# S2_Mini_Benchtop_Test_Board.net
KiCad netlist of a schematic drawn in EAGLE
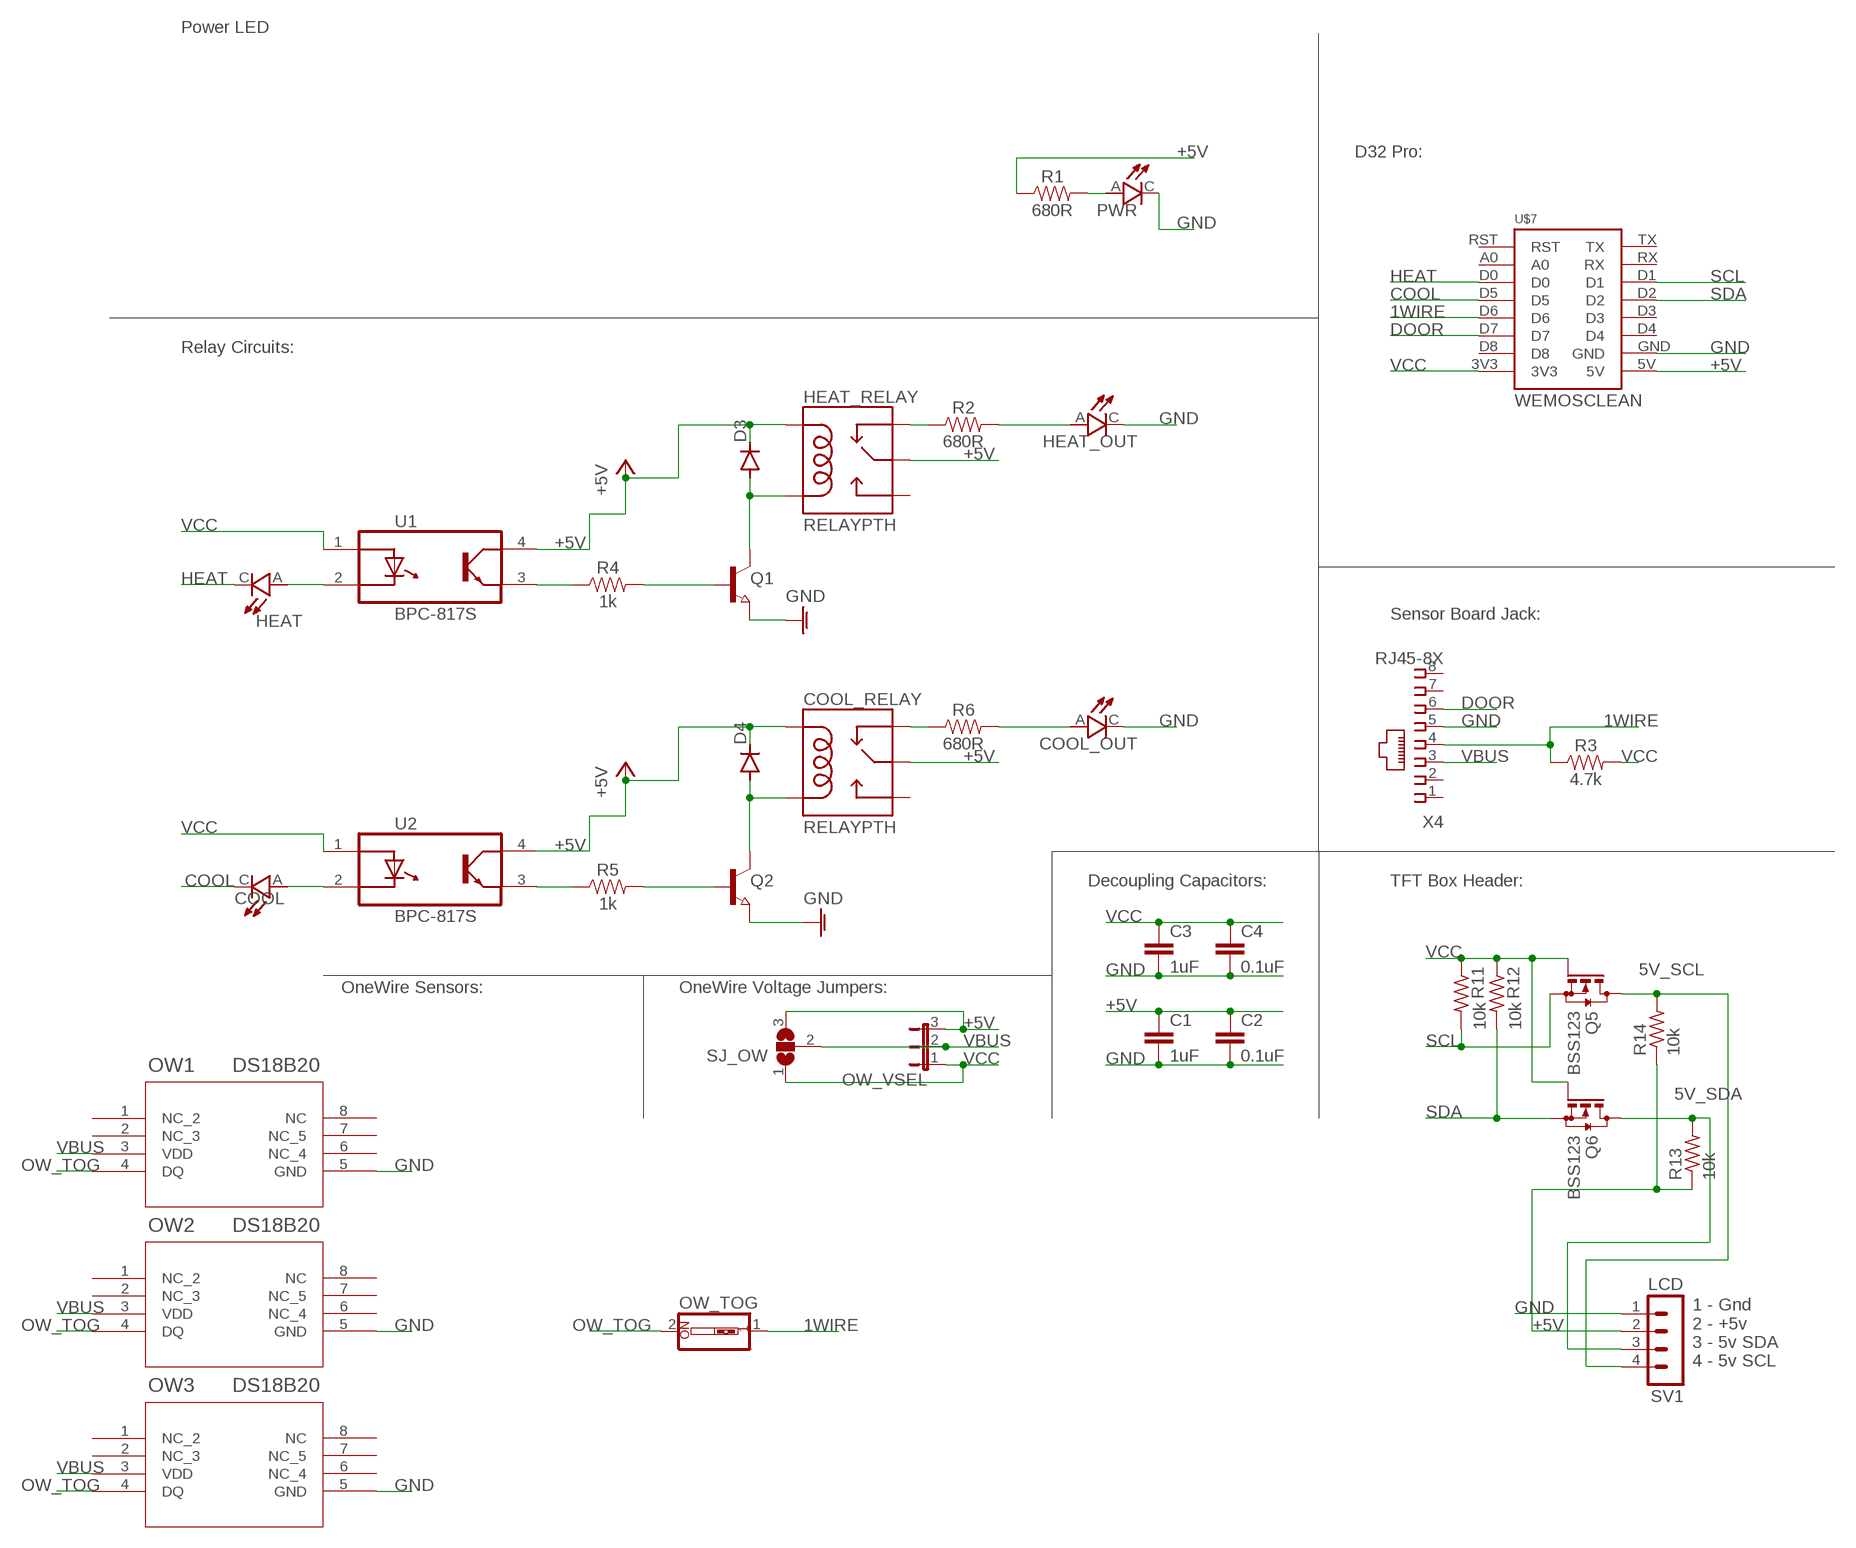
[diagram p0: schematic, sheet 1]

(export (version "E")
  (design (tool "Eeschema 10.0.6"))
  (components
    (comp (ref "C1")
      (value "1uF")
      (footprint "eagle-import:SMD-0805")
      (fields (field (name "LCSC_PART") "C28323"))
      (libsource (lib "eagle-import") (part "CAP_SMD0805"))
    )
    (comp (ref "C2")
      (value "0.1uF")
      (footprint "eagle-import:SMD-0805")
      (fields (field (name "LCSC_PART") "C49678"))
      (libsource (lib "eagle-import") (part "CAP_SMD0805"))
    )
    (comp (ref "C3")
      (value "1uF")
      (footprint "eagle-import:SMD-0805")
      (fields (field (name "LCSC_PART") "C28323"))
      (libsource (lib "eagle-import") (part "CAP_SMD0805"))
    )
    (comp (ref "C4")
      (value "0.1uF")
      (footprint "eagle-import:SMD-0805")
      (fields (field (name "LCSC_PART") "C49678"))
      (libsource (lib "eagle-import") (part "CAP_SMD0805"))
    )
    (comp (ref "COOL")
      (value "LED_0603LED_SMD_0603")
      (footprint "eagle-import:LED_SMD_0603")
      (fields (field (name "LCSC_PART") "C2286") (field (name "LCSC_PART_1") "C2286"))
      (libsource (lib "eagle-import") (part "LED_0603LED_SMD_0603"))
    )
    (comp (ref "COOL_OUT")
      (value "LED_0603LED_SMD_0603")
      (footprint "eagle-import:LED_SMD_0603")
      (fields (field (name "LCSC_PART") "C2286"))
      (libsource (lib "eagle-import") (part "LED_0603LED_SMD_0603"))
    )
    (comp (ref "COOL_RELAY")
      (value "RELAYPTH")
      (footprint "eagle-import:SRD-05VDC-SL-C")
      (fields (field (name "LCSC_PART") "C35449"))
      (libsource (lib "eagle-import") (part "RELAYPTH"))
    )
    (comp (ref "D3")
      (value "DIODE-DO214AC")
      (footprint "eagle-import:DO214AC")
      (fields (field (name "LCSC_PART") "C95872"))
      (libsource (lib "eagle-import") (part "DIODE-DO214AC"))
    )
    (comp (ref "D4")
      (value "DIODE-DO214AC")
      (footprint "eagle-import:DO214AC")
      (fields (field (name "LCSC_PART") "C95872"))
      (libsource (lib "eagle-import") (part "DIODE-DO214AC"))
    )
    (comp (ref "HEAT")
      (value "LED_0603LED_SMD_0603")
      (footprint "eagle-import:LED_SMD_0603")
      (fields (field (name "LCSC_PART") "C2286") (field (name "LCSC_PART_1") "C2286"))
      (libsource (lib "eagle-import") (part "LED_0603LED_SMD_0603"))
    )
    (comp (ref "HEAT_OUT")
      (value "LED_0603LED_SMD_0603")
      (footprint "eagle-import:LED_SMD_0603")
      (fields (field (name "LCSC_PART") "C2286"))
      (libsource (lib "eagle-import") (part "LED_0603LED_SMD_0603"))
    )
    (comp (ref "HEAT_RELAY")
      (value "RELAYPTH")
      (footprint "eagle-import:SRD-05VDC-SL-C")
      (fields (field (name "LCSC_PART") "C35449"))
      (libsource (lib "eagle-import") (part "RELAYPTH"))
    )
    (comp (ref "OW1")
      (value "DS18B20")
      (footprint "eagle-import:21-0041B_8_MXM")
      (fields
        (field (name "LCSC_PART") "C695837")
        (field (name "MANUFACTURER_PART_NUMBER") "DS18B20Z+T&R")
        (field (name "COPYRIGHT") "Copyright (C) 2024 Ultra Librarian. All rights reserved.")
      )
      (libsource (lib "eagle-import") (part "DS18B20Z+T&R"))
    )
    (comp (ref "OW2")
      (value "DS18B20")
      (footprint "eagle-import:21-0041B_8_MXM")
      (fields
        (field (name "LCSC_PART") "C695837")
        (field (name "MANUFACTURER_PART_NUMBER") "DS18B20Z+T&R")
        (field (name "COPYRIGHT") "Copyright (C) 2024 Ultra Librarian. All rights reserved.")
      )
      (libsource (lib "eagle-import") (part "DS18B20Z+T&R"))
    )
    (comp (ref "OW3")
      (value "DS18B20")
      (footprint "eagle-import:21-0041B_8_MXM")
      (fields
        (field (name "LCSC_PART") "C695837")
        (field (name "MANUFACTURER_PART_NUMBER") "DS18B20Z+T&R")
        (field (name "COPYRIGHT") "Copyright (C) 2024 Ultra Librarian. All rights reserved.")
      )
      (libsource (lib "eagle-import") (part "DS18B20Z+T&R"))
    )
    (comp (ref "OW_TOG")
      (value "SW_DIP-1")
      (footprint "eagle-import:EDG-01")
      (fields (field (name "LCSC_PART") "C126888"))
      (libsource (lib "eagle-import") (part "SW_DIP-1"))
    )
    (comp (ref "OW_VSEL")
      (value "JP2ENOLABEL")
      (footprint "eagle-import:JP2-NOLABEL")
      (fields (field (name "LCSC_PART") "C2937625"))
      (libsource (lib "eagle-import") (part "JP2ENOLABEL"))
    )
    (comp (ref "PWR")
      (value "LED_0603LED_SMD_0603")
      (footprint "eagle-import:LED_SMD_0603")
      (fields (field (name "LCSC_PART") "C2286") (field (name "LCSC_PART_1") "C2286"))
      (libsource (lib "eagle-import") (part "LED_0603LED_SMD_0603"))
    )
    (comp (ref "Q1")
      (value "NPN-TRANSISTOR_SOT23")
      (footprint "eagle-import:SOT23")
      (fields (field (name "LCSC_PART") "C20526"))
      (libsource (lib "eagle-import") (part "NPN-TRANSISTOR_SOT23"))
    )
    (comp (ref "Q2")
      (value "NPN-TRANSISTOR_SOT23")
      (footprint "eagle-import:SOT23")
      (fields (field (name "LCSC_PART") "C20526"))
      (libsource (lib "eagle-import") (part "NPN-TRANSISTOR_SOT23"))
    )
    (comp (ref "Q5")
      (value "BSS123")
      (footprint "eagle-import:SOT23")
      (fields (field (name "LCSC_PART") "C79015"))
      (libsource (lib "eagle-import") (part "BSS123"))
    )
    (comp (ref "Q6")
      (value "BSS123")
      (footprint "eagle-import:SOT23")
      (fields (field (name "LCSC_PART") "C79015"))
      (libsource (lib "eagle-import") (part "BSS123"))
    )
    (comp (ref "R1")
      (value "680R")
      (footprint "eagle-import:SMD-0805")
      (fields (field (name "LCSC_PART") "C17798"))
      (libsource (lib "eagle-import") (part "RES_SMD0805"))
    )
    (comp (ref "R2")
      (value "680R")
      (footprint "eagle-import:SMD-0805")
      (fields (field (name "LCSC_PART") "C17798"))
      (libsource (lib "eagle-import") (part "RES_SMD0805"))
    )
    (comp (ref "R3")
      (value "4.7k")
      (footprint "eagle-import:SMD-0805")
      (fields (field (name "LCSC_PART") "C17673"))
      (libsource (lib "eagle-import") (part "RES_SMD0805"))
    )
    (comp (ref "R4")
      (value "1k")
      (footprint "eagle-import:SMD-0805")
      (fields (field (name "LCSC_PART") "C17513"))
      (libsource (lib "eagle-import") (part "RES_SMD0805"))
    )
    (comp (ref "R5")
      (value "1k")
      (footprint "eagle-import:SMD-0805")
      (fields (field (name "LCSC_PART") "C17513"))
      (libsource (lib "eagle-import") (part "RES_SMD0805"))
    )
    (comp (ref "R6")
      (value "680R")
      (footprint "eagle-import:SMD-0805")
      (fields (field (name "LCSC_PART") "C17798"))
      (libsource (lib "eagle-import") (part "RES_SMD0805"))
    )
    (comp (ref "R11")
      (value "10k")
      (footprint "eagle-import:R0805")
      (fields (field (name "LCSC_PART") "C17902"))
      (libsource (lib "eagle-import") (part "R-US_R0805"))
    )
    (comp (ref "R12")
      (value "10k")
      (footprint "eagle-import:R0805")
      (fields (field (name "LCSC_PART") "C17902"))
      (libsource (lib "eagle-import") (part "R-US_R0805"))
    )
    (comp (ref "R13")
      (value "10k")
      (footprint "eagle-import:R0805")
      (fields (field (name "LCSC_PART") "C17902"))
      (libsource (lib "eagle-import") (part "R-US_R0805"))
    )
    (comp (ref "R14")
      (value "10k")
      (footprint "eagle-import:R0805")
      (fields (field (name "LCSC_PART") "C17902"))
      (libsource (lib "eagle-import") (part "R-US_R0805"))
    )
    (comp (ref "SJ_OW")
      (value "SJ2W")
      (footprint "eagle-import:SJ_2")
      (libsource (lib "eagle-import") (part "SJ2W"))
    )
    (comp (ref "SV1")
      (value "LCD")
      (footprint "eagle-import:HDR-4_VERT")
      (fields (field (name "LCSC_PART") "C2691448"))
      (libsource (lib "eagle-import") (part "HDR-4"))
    )
    (comp (ref "U$7")
      (value "WEMOSCLEAN")
      (footprint "eagle-import:WEMOS-CLEAN")
      (libsource (lib "eagle-import") (part "WEMOSCLEAN"))
    )
    (comp (ref "U1")
      (value "BPC-817S")
      (footprint "eagle-import:SOIC127P700X210-4N")
      (fields (field (name "LCSC_PART") "C106900"))
      (libsource (lib "eagle-import") (part "BPC-817S"))
    )
    (comp (ref "U2")
      (value "BPC-817S")
      (footprint "eagle-import:SOIC127P700X210-4N")
      (fields (field (name "LCSC_PART") "C106900"))
      (libsource (lib "eagle-import") (part "BPC-817S"))
    )
    (comp (ref "X4")
      (value "RJ45-8X")
      (footprint "eagle-import:RJ45-NO-SHIELD")
      (fields
        (field (name "LCSC_PART") "C3000197")
        (field (name "JLC_Y") "7.55")
        (field (name "LCSC_PART_1") "C3000197")
      )
      (libsource (lib "eagle-import") (part "RJ45-8X"))
    )
  )
  (nets
    (net (code "1") (name "+5V") (class "Default")
      (node (ref "C1") (pin "1") (pinfunction "1_1") (pintype "passive"))
      (node (ref "C2") (pin "1") (pinfunction "1_1") (pintype "passive"))
      (node (ref "COOL_RELAY") (pin "COIL1") (pinfunction "COIL1_COIL1") (pintype "bidirectional"))
      (node (ref "COOL_RELAY") (pin "SWCOMMON") (pinfunction "SWCOMMON_SWCOMMON") (pintype "bidirectional"))
      (node (ref "D3") (pin "C") (pinfunction "C_C") (pintype "passive"))
      (node (ref "D4") (pin "C") (pinfunction "C_C") (pintype "passive"))
      (node (ref "HEAT_RELAY") (pin "COIL1") (pinfunction "COIL1_COIL1") (pintype "bidirectional"))
      (node (ref "HEAT_RELAY") (pin "SWCOMMON") (pinfunction "SWCOMMON_SWCOMMON") (pintype "bidirectional"))
      (node (ref "OW_VSEL") (pin "3") (pinfunction "3_3") (pintype "passive"))
      (node (ref "R1") (pin "1") (pinfunction "1_1") (pintype "passive"))
      (node (ref "R13") (pin "1") (pinfunction "1_1") (pintype "passive"))
      (node (ref "R14") (pin "1") (pinfunction "1_1") (pintype "passive"))
      (node (ref "SJ_OW") (pin "3") (pinfunction "3_3") (pintype "passive"))
      (node (ref "SV1") (pin "2") (pinfunction "2_2") (pintype "passive"))
      (node (ref "U$7") (pin "5V") (pinfunction "5V_5V") (pintype "bidirectional"))
      (node (ref "U1") (pin "4") (pinfunction "CO_4") (pintype "passive"))
      (node (ref "U2") (pin "4") (pinfunction "CO_4") (pintype "passive"))
    )
    (net (code "2") (name "/1WIRE") (class "Default")
      (node (ref "OW_TOG") (pin "1") (pinfunction "1_1") (pintype "passive"))
      (node (ref "R3") (pin "1") (pinfunction "1_1") (pintype "passive"))
      (node (ref "U$7") (pin "D6") (pinfunction "D6_D6") (pintype "bidirectional"))
      (node (ref "X4") (pin "4") (pinfunction "4_4") (pintype "passive"))
    )
    (net (code "3") (name "/5V_SCL") (class "Default")
      (node (ref "Q5") (pin "3") (pinfunction "D_3") (pintype "passive"))
      (node (ref "R14") (pin "2") (pinfunction "2_2") (pintype "passive"))
      (node (ref "SV1") (pin "4") (pinfunction "4_4") (pintype "passive"))
    )
    (net (code "4") (name "/5V_SDA") (class "Default")
      (node (ref "Q6") (pin "3") (pinfunction "D_3") (pintype "passive"))
      (node (ref "R13") (pin "2") (pinfunction "2_2") (pintype "passive"))
      (node (ref "SV1") (pin "3") (pinfunction "3_3") (pintype "passive"))
    )
    (net (code "5") (name "/COOL") (class "Default")
      (node (ref "COOL") (pin "C") (pinfunction "C_C") (pintype "passive"))
      (node (ref "U$7") (pin "D5") (pinfunction "D5_D5") (pintype "bidirectional"))
    )
    (net (code "6") (name "/DOOR") (class "Default")
      (node (ref "U$7") (pin "D7") (pinfunction "D7_D7") (pintype "bidirectional"))
      (node (ref "X4") (pin "6") (pinfunction "6_6") (pintype "passive"))
    )
    (net (code "7") (name "/HEAT") (class "Default")
      (node (ref "HEAT") (pin "C") (pinfunction "C_C") (pintype "passive"))
      (node (ref "U$7") (pin "D0") (pinfunction "D0_D0") (pintype "bidirectional"))
    )
    (net (code "8") (name "/OW_TOG") (class "Default")
      (node (ref "OW1") (pin "4") (pinfunction "DQ_4") (pintype "bidirectional"))
      (node (ref "OW2") (pin "4") (pinfunction "DQ_4") (pintype "bidirectional"))
      (node (ref "OW3") (pin "4") (pinfunction "DQ_4") (pintype "bidirectional"))
      (node (ref "OW_TOG") (pin "2") (pinfunction "2_2") (pintype "passive"))
    )
    (net (code "9") (name "/SCL") (class "Default")
      (node (ref "Q5") (pin "2") (pinfunction "S_2") (pintype "passive"))
      (node (ref "R11") (pin "2") (pinfunction "2_2") (pintype "passive"))
      (node (ref "U$7") (pin "D1") (pinfunction "D1_D1") (pintype "bidirectional"))
    )
    (net (code "10") (name "/SDA") (class "Default")
      (node (ref "Q6") (pin "2") (pinfunction "S_2") (pintype "passive"))
      (node (ref "R12") (pin "2") (pinfunction "2_2") (pintype "passive"))
      (node (ref "U$7") (pin "D2") (pinfunction "D2_D2") (pintype "bidirectional"))
    )
    (net (code "11") (name "/VBUS") (class "Default")
      (node (ref "OW1") (pin "3") (pinfunction "VDD_3") (pintype "power_in"))
      (node (ref "OW2") (pin "3") (pinfunction "VDD_3") (pintype "power_in"))
      (node (ref "OW3") (pin "3") (pinfunction "VDD_3") (pintype "power_in"))
      (node (ref "OW_VSEL") (pin "2") (pinfunction "2_2") (pintype "passive"))
      (node (ref "SJ_OW") (pin "2") (pinfunction "2_2") (pintype "passive"))
      (node (ref "X4") (pin "3") (pinfunction "3_3") (pintype "passive"))
    )
    (net (code "12") (name "/VCC") (class "Default")
      (node (ref "C3") (pin "1") (pinfunction "1_1") (pintype "passive"))
      (node (ref "C4") (pin "1") (pinfunction "1_1") (pintype "passive"))
      (node (ref "OW_VSEL") (pin "1") (pinfunction "1_1") (pintype "passive"))
      (node (ref "Q5") (pin "1") (pinfunction "G_1") (pintype "passive"))
      (node (ref "Q6") (pin "1") (pinfunction "G_1") (pintype "passive"))
      (node (ref "R11") (pin "1") (pinfunction "1_1") (pintype "passive"))
      (node (ref "R12") (pin "1") (pinfunction "1_1") (pintype "passive"))
      (node (ref "R3") (pin "2") (pinfunction "2_2") (pintype "passive"))
      (node (ref "SJ_OW") (pin "1") (pinfunction "1_1") (pintype "passive"))
      (node (ref "U$7") (pin "3V3") (pinfunction "3V3_3V3") (pintype "bidirectional"))
      (node (ref "U1") (pin "1") (pinfunction "A_1") (pintype "passive"))
      (node (ref "U2") (pin "1") (pinfunction "A_1") (pintype "passive"))
    )
    (net (code "13") (name "GNDA") (class "Default")
      (node (ref "C1") (pin "2") (pinfunction "2_2") (pintype "passive"))
      (node (ref "C2") (pin "2") (pinfunction "2_2") (pintype "passive"))
      (node (ref "C3") (pin "2") (pinfunction "2_2") (pintype "passive"))
      (node (ref "C4") (pin "2") (pinfunction "2_2") (pintype "passive"))
      (node (ref "COOL_OUT") (pin "C") (pinfunction "C_C") (pintype "passive"))
      (node (ref "HEAT_OUT") (pin "C") (pinfunction "C_C") (pintype "passive"))
      (node (ref "OW1") (pin "5") (pinfunction "GND_5") (pintype "power_in"))
      (node (ref "OW2") (pin "5") (pinfunction "GND_5") (pintype "power_in"))
      (node (ref "OW3") (pin "5") (pinfunction "GND_5") (pintype "power_in"))
      (node (ref "PWR") (pin "C") (pinfunction "C_C") (pintype "passive"))
      (node (ref "Q1") (pin "2") (pinfunction "E_2") (pintype "passive"))
      (node (ref "Q2") (pin "2") (pinfunction "E_2") (pintype "passive"))
      (node (ref "SV1") (pin "1") (pinfunction "1_1") (pintype "passive"))
      (node (ref "U$7") (pin "GND") (pinfunction "GND_GND") (pintype "bidirectional"))
      (node (ref "X4") (pin "5") (pinfunction "5_5") (pintype "passive"))
    )
    (net (code "14") (name "Net-(COOL_OUT-PadA)") (class "Default")
      (node (ref "COOL_OUT") (pin "A") (pinfunction "A_A") (pintype "passive"))
      (node (ref "R6") (pin "2") (pinfunction "2_2") (pintype "passive"))
    )
    (net (code "15") (name "Net-(COOL_RELAY-SWCLOSE)") (class "Default")
      (node (ref "COOL_RELAY") (pin "SWCLOSED") (pinfunction "SWCLOSE_SWCLOSED") (pintype "bidirectional"))
      (node (ref "R6") (pin "1") (pinfunction "1_1") (pintype "passive"))
    )
    (net (code "16") (name "Net-(HEAT_OUT-PadA)") (class "Default")
      (node (ref "HEAT_OUT") (pin "A") (pinfunction "A_A") (pintype "passive"))
      (node (ref "R2") (pin "2") (pinfunction "2_2") (pintype "passive"))
    )
    (net (code "17") (name "Net-(HEAT_RELAY-SWCLOSE)") (class "Default")
      (node (ref "HEAT_RELAY") (pin "SWCLOSED") (pinfunction "SWCLOSE_SWCLOSED") (pintype "bidirectional"))
      (node (ref "R2") (pin "1") (pinfunction "1_1") (pintype "passive"))
    )
    (net (code "18") (name "Net-(PWR-PadA)") (class "Default")
      (node (ref "PWR") (pin "A") (pinfunction "A_A") (pintype "passive"))
      (node (ref "R1") (pin "2") (pinfunction "2_2") (pintype "passive"))
    )
    (net (code "19") (name "Net-(Q1-B)") (class "Default")
      (node (ref "Q1") (pin "1") (pinfunction "B_1") (pintype "passive"))
      (node (ref "R4") (pin "2") (pinfunction "2_2") (pintype "passive"))
    )
    (net (code "20") (name "Net-(Q1-C)") (class "Default")
      (node (ref "D3") (pin "A") (pinfunction "A_A") (pintype "passive"))
      (node (ref "HEAT_RELAY") (pin "COIL0") (pinfunction "COIL0_COIL0") (pintype "bidirectional"))
      (node (ref "Q1") (pin "3") (pinfunction "C_3") (pintype "passive"))
    )
    (net (code "21") (name "Net-(Q2-B)") (class "Default")
      (node (ref "Q2") (pin "1") (pinfunction "B_1") (pintype "passive"))
      (node (ref "R5") (pin "2") (pinfunction "2_2") (pintype "passive"))
    )
    (net (code "22") (name "Net-(Q2-C)") (class "Default")
      (node (ref "COOL_RELAY") (pin "COIL0") (pinfunction "COIL0_COIL0") (pintype "bidirectional"))
      (node (ref "D4") (pin "A") (pinfunction "A_A") (pintype "passive"))
      (node (ref "Q2") (pin "3") (pinfunction "C_3") (pintype "passive"))
    )
    (net (code "23") (name "Net-(U1-C)") (class "Default")
      (node (ref "HEAT") (pin "A") (pinfunction "A_A") (pintype "passive"))
      (node (ref "U1") (pin "2") (pinfunction "C_2") (pintype "passive"))
    )
    (net (code "24") (name "Net-(U1-E)") (class "Default")
      (node (ref "R4") (pin "1") (pinfunction "1_1") (pintype "passive"))
      (node (ref "U1") (pin "3") (pinfunction "E_3") (pintype "passive"))
    )
    (net (code "25") (name "Net-(U2-C)") (class "Default")
      (node (ref "COOL") (pin "A") (pinfunction "A_A") (pintype "passive"))
      (node (ref "U2") (pin "2") (pinfunction "C_2") (pintype "passive"))
    )
    (net (code "26") (name "Net-(U2-E)") (class "Default")
      (node (ref "R5") (pin "1") (pinfunction "1_1") (pintype "passive"))
      (node (ref "U2") (pin "3") (pinfunction "E_3") (pintype "passive"))
    )
    (net (code "27") (name "unconnected-(COOL_RELAY-PadSWOPEN)") (class "Default")
      (node (ref "COOL_RELAY") (pin "SWOPEN") (pinfunction "SWOPEN_SWOPEN") (pintype "bidirectional"))
    )
    (net (code "28") (name "unconnected-(HEAT_RELAY-PadSWOPEN)") (class "Default")
      (node (ref "HEAT_RELAY") (pin "SWOPEN") (pinfunction "SWOPEN_SWOPEN") (pintype "bidirectional"))
    )
    (net (code "29") (name "unconnected-(OW1-NC-Pad8)") (class "Default")
      (node (ref "OW1") (pin "8") (pinfunction "NC_8") (pintype "no_connect"))
    )
    (net (code "30") (name "unconnected-(OW1-NC_2-Pad1)") (class "Default")
      (node (ref "OW1") (pin "1") (pinfunction "NC_2_1") (pintype "no_connect"))
    )
    (net (code "31") (name "unconnected-(OW1-NC_3-Pad2)") (class "Default")
      (node (ref "OW1") (pin "2") (pinfunction "NC_3_2") (pintype "no_connect"))
    )
    (net (code "32") (name "unconnected-(OW1-NC_4-Pad6)") (class "Default")
      (node (ref "OW1") (pin "6") (pinfunction "NC_4_6") (pintype "no_connect"))
    )
    (net (code "33") (name "unconnected-(OW1-NC_5-Pad7)") (class "Default")
      (node (ref "OW1") (pin "7") (pinfunction "NC_5_7") (pintype "no_connect"))
    )
    (net (code "34") (name "unconnected-(OW2-NC-Pad8)") (class "Default")
      (node (ref "OW2") (pin "8") (pinfunction "NC_8") (pintype "no_connect"))
    )
    (net (code "35") (name "unconnected-(OW2-NC_2-Pad1)") (class "Default")
      (node (ref "OW2") (pin "1") (pinfunction "NC_2_1") (pintype "no_connect"))
    )
    (net (code "36") (name "unconnected-(OW2-NC_3-Pad2)") (class "Default")
      (node (ref "OW2") (pin "2") (pinfunction "NC_3_2") (pintype "no_connect"))
    )
    (net (code "37") (name "unconnected-(OW2-NC_4-Pad6)") (class "Default")
      (node (ref "OW2") (pin "6") (pinfunction "NC_4_6") (pintype "no_connect"))
    )
    (net (code "38") (name "unconnected-(OW2-NC_5-Pad7)") (class "Default")
      (node (ref "OW2") (pin "7") (pinfunction "NC_5_7") (pintype "no_connect"))
    )
    (net (code "39") (name "unconnected-(OW3-NC-Pad8)") (class "Default")
      (node (ref "OW3") (pin "8") (pinfunction "NC_8") (pintype "no_connect"))
    )
    (net (code "40") (name "unconnected-(OW3-NC_2-Pad1)") (class "Default")
      (node (ref "OW3") (pin "1") (pinfunction "NC_2_1") (pintype "no_connect"))
    )
    (net (code "41") (name "unconnected-(OW3-NC_3-Pad2)") (class "Default")
      (node (ref "OW3") (pin "2") (pinfunction "NC_3_2") (pintype "no_connect"))
    )
    (net (code "42") (name "unconnected-(OW3-NC_4-Pad6)") (class "Default")
      (node (ref "OW3") (pin "6") (pinfunction "NC_4_6") (pintype "no_connect"))
    )
    (net (code "43") (name "unconnected-(OW3-NC_5-Pad7)") (class "Default")
      (node (ref "OW3") (pin "7") (pinfunction "NC_5_7") (pintype "no_connect"))
    )
    (net (code "44") (name "unconnected-(U$7-PadA0)") (class "Default")
      (node (ref "U$7") (pin "A0") (pinfunction "A0_A0") (pintype "bidirectional"))
    )
    (net (code "45") (name "unconnected-(U$7-PadD3)") (class "Default")
      (node (ref "U$7") (pin "D3") (pinfunction "D3_D3") (pintype "bidirectional"))
    )
    (net (code "46") (name "unconnected-(U$7-PadD4)") (class "Default")
      (node (ref "U$7") (pin "D4") (pinfunction "D4_D4") (pintype "bidirectional"))
    )
    (net (code "47") (name "unconnected-(U$7-PadD8)") (class "Default")
      (node (ref "U$7") (pin "D8") (pinfunction "D8_D8") (pintype "bidirectional"))
    )
    (net (code "48") (name "unconnected-(U$7-PadRST)") (class "Default")
      (node (ref "U$7") (pin "RST") (pinfunction "RST_RST") (pintype "bidirectional"))
    )
    (net (code "49") (name "unconnected-(U$7-PadRX)") (class "Default")
      (node (ref "U$7") (pin "RX") (pinfunction "RX_RX") (pintype "bidirectional"))
    )
    (net (code "50") (name "unconnected-(U$7-PadTX)") (class "Default")
      (node (ref "U$7") (pin "TX") (pinfunction "TX_TX") (pintype "bidirectional"))
    )
    (net (code "51") (name "unconnected-(X4-Pad1)") (class "Default")
      (node (ref "X4") (pin "1") (pinfunction "1_1") (pintype "passive"))
    )
    (net (code "52") (name "unconnected-(X4-Pad2)") (class "Default")
      (node (ref "X4") (pin "2") (pinfunction "2_2") (pintype "passive"))
    )
    (net (code "53") (name "unconnected-(X4-Pad7)") (class "Default")
      (node (ref "X4") (pin "7") (pinfunction "7_7") (pintype "passive"))
    )
    (net (code "54") (name "unconnected-(X4-Pad8)") (class "Default")
      (node (ref "X4") (pin "8") (pinfunction "8_8") (pintype "passive"))
    )
  )
)
